# 0402-capacitor-shunt-2x.net
KiCad netlist of a schematic drawn in EAGLE
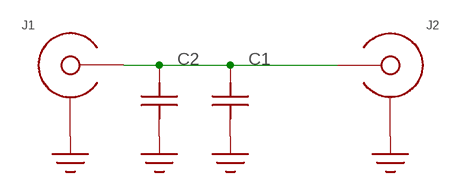
[diagram p0: schematic, sheet 1]

(export (version "E")
  (design (tool "Eeschema 10.0.6"))
  (components
    (comp (ref "C1") (value "C") (footprint "eagle-import:C0402") (libsource (lib "eagle-import") (part "C")))
    (comp (ref "C2") (value "C") (footprint "eagle-import:C0402") (libsource (lib "eagle-import") (part "C")))
    (comp (ref "J1")
      (value "SMA-EDGE-LAUNCH4020_TAPER")
      (footprint "eagle-import:SMA_EDGE_LAUNCH_2L_4020_TAPER")
      (libsource (lib "eagle-import") (part "SMA-EDGE-LAUNCH4020_TAPER"))
    )
    (comp (ref "J2")
      (value "SMA-EDGE-LAUNCHCUT-PIN")
      (footprint "eagle-import:SMA_EDGE_LAUNCH_2L_4020_CUT_PIN")
      (libsource (lib "eagle-import") (part "SMA-EDGE-LAUNCHCUT-PIN"))
    )
  )
  (nets
    (net (code "1") (name "GND") (class "Default")
      (node (ref "C1") (pin "1") (pinfunction "P$1_1") (pintype "bidirectional"))
      (node (ref "C2") (pin "1") (pinfunction "P$1_1") (pintype "bidirectional"))
      (node (ref "J1") (pin "BOTTOM_GND") (pinfunction "SHIELD_BOTTOM_GND") (pintype "bidirectional"))
      (node (ref "J1") (pin "GND@1") (pinfunction "SHIELD_GND@1") (pintype "bidirectional"))
      (node (ref "J1") (pin "GND@14") (pinfunction "SHIELD_GND@14") (pintype "bidirectional"))
      (node (ref "J1") (pin "GND@15") (pinfunction "SHIELD_GND@15") (pintype "bidirectional"))
      (node (ref "J1") (pin "GND@16") (pinfunction "SHIELD_GND@16") (pintype "bidirectional"))
      (node (ref "J1") (pin "GND@17") (pinfunction "SHIELD_GND@17") (pintype "bidirectional"))
      (node (ref "J1") (pin "GND@2") (pinfunction "SHIELD_GND@2") (pintype "bidirectional"))
      (node (ref "J1") (pin "GND@3") (pinfunction "SHIELD_GND@3") (pintype "bidirectional"))
      (node (ref "J1") (pin "GND@4") (pinfunction "SHIELD_GND@4") (pintype "bidirectional"))
      (node (ref "J1") (pin "GND@5") (pinfunction "SHIELD_GND@5") (pintype "bidirectional"))
      (node (ref "J1") (pin "GND@6") (pinfunction "SHIELD_GND@6") (pintype "bidirectional"))
      (node (ref "J1") (pin "GND@7") (pinfunction "SHIELD_GND@7") (pintype "bidirectional"))
      (node (ref "J1") (pin "GND@8") (pinfunction "SHIELD_GND@8") (pintype "bidirectional"))
      (node (ref "J1") (pin "GND_PAD1") (pinfunction "SHIELD_GND_PAD1") (pintype "bidirectional"))
      (node (ref "J1") (pin "GND_PAD2") (pinfunction "SHIELD_GND_PAD2") (pintype "bidirectional"))
      (node (ref "J1") (pin "P$1") (pinfunction "SHIELD_P$1") (pintype "bidirectional"))
      (node (ref "J1") (pin "P$2") (pinfunction "SHIELD_P$2") (pintype "bidirectional"))
      (node (ref "J2") (pin "BOTTOM_GND") (pinfunction "SHIELD_BOTTOM_GND") (pintype "bidirectional"))
      (node (ref "J2") (pin "GND@1") (pinfunction "SHIELD_GND@1") (pintype "bidirectional"))
      (node (ref "J2") (pin "GND@14") (pinfunction "SHIELD_GND@14") (pintype "bidirectional"))
      (node (ref "J2") (pin "GND@15") (pinfunction "SHIELD_GND@15") (pintype "bidirectional"))
      (node (ref "J2") (pin "GND@16") (pinfunction "SHIELD_GND@16") (pintype "bidirectional"))
      (node (ref "J2") (pin "GND@17") (pinfunction "SHIELD_GND@17") (pintype "bidirectional"))
      (node (ref "J2") (pin "GND@2") (pinfunction "SHIELD_GND@2") (pintype "bidirectional"))
      (node (ref "J2") (pin "GND@3") (pinfunction "SHIELD_GND@3") (pintype "bidirectional"))
      (node (ref "J2") (pin "GND@4") (pinfunction "SHIELD_GND@4") (pintype "bidirectional"))
      (node (ref "J2") (pin "GND@5") (pinfunction "SHIELD_GND@5") (pintype "bidirectional"))
      (node (ref "J2") (pin "GND@6") (pinfunction "SHIELD_GND@6") (pintype "bidirectional"))
      (node (ref "J2") (pin "GND@7") (pinfunction "SHIELD_GND@7") (pintype "bidirectional"))
      (node (ref "J2") (pin "GND@8") (pinfunction "SHIELD_GND@8") (pintype "bidirectional"))
      (node (ref "J2") (pin "GND_PAD1") (pinfunction "SHIELD_GND_PAD1") (pintype "bidirectional"))
      (node (ref "J2") (pin "GND_PAD2") (pinfunction "SHIELD_GND_PAD2") (pintype "bidirectional"))
    )
    (net (code "2") (name "Net-(C1-P$2)") (class "Default")
      (node (ref "C1") (pin "2") (pinfunction "P$2_2") (pintype "bidirectional"))
      (node (ref "C2") (pin "2") (pinfunction "P$2_2") (pintype "bidirectional"))
      (node (ref "J1") (pin "CENTER@1") (pinfunction "CENTER_CENTER@1") (pintype "bidirectional"))
      (node (ref "J2") (pin "CENTER@1") (pinfunction "CENTER_CENTER@1") (pintype "bidirectional"))
      (node (ref "J2") (pin "CENTER@3") (pinfunction "CENTER_CENTER@3") (pintype "bidirectional"))
    )
  )
)
